# StickLogger.net
KiCad netlist of a schematic drawn in EAGLE
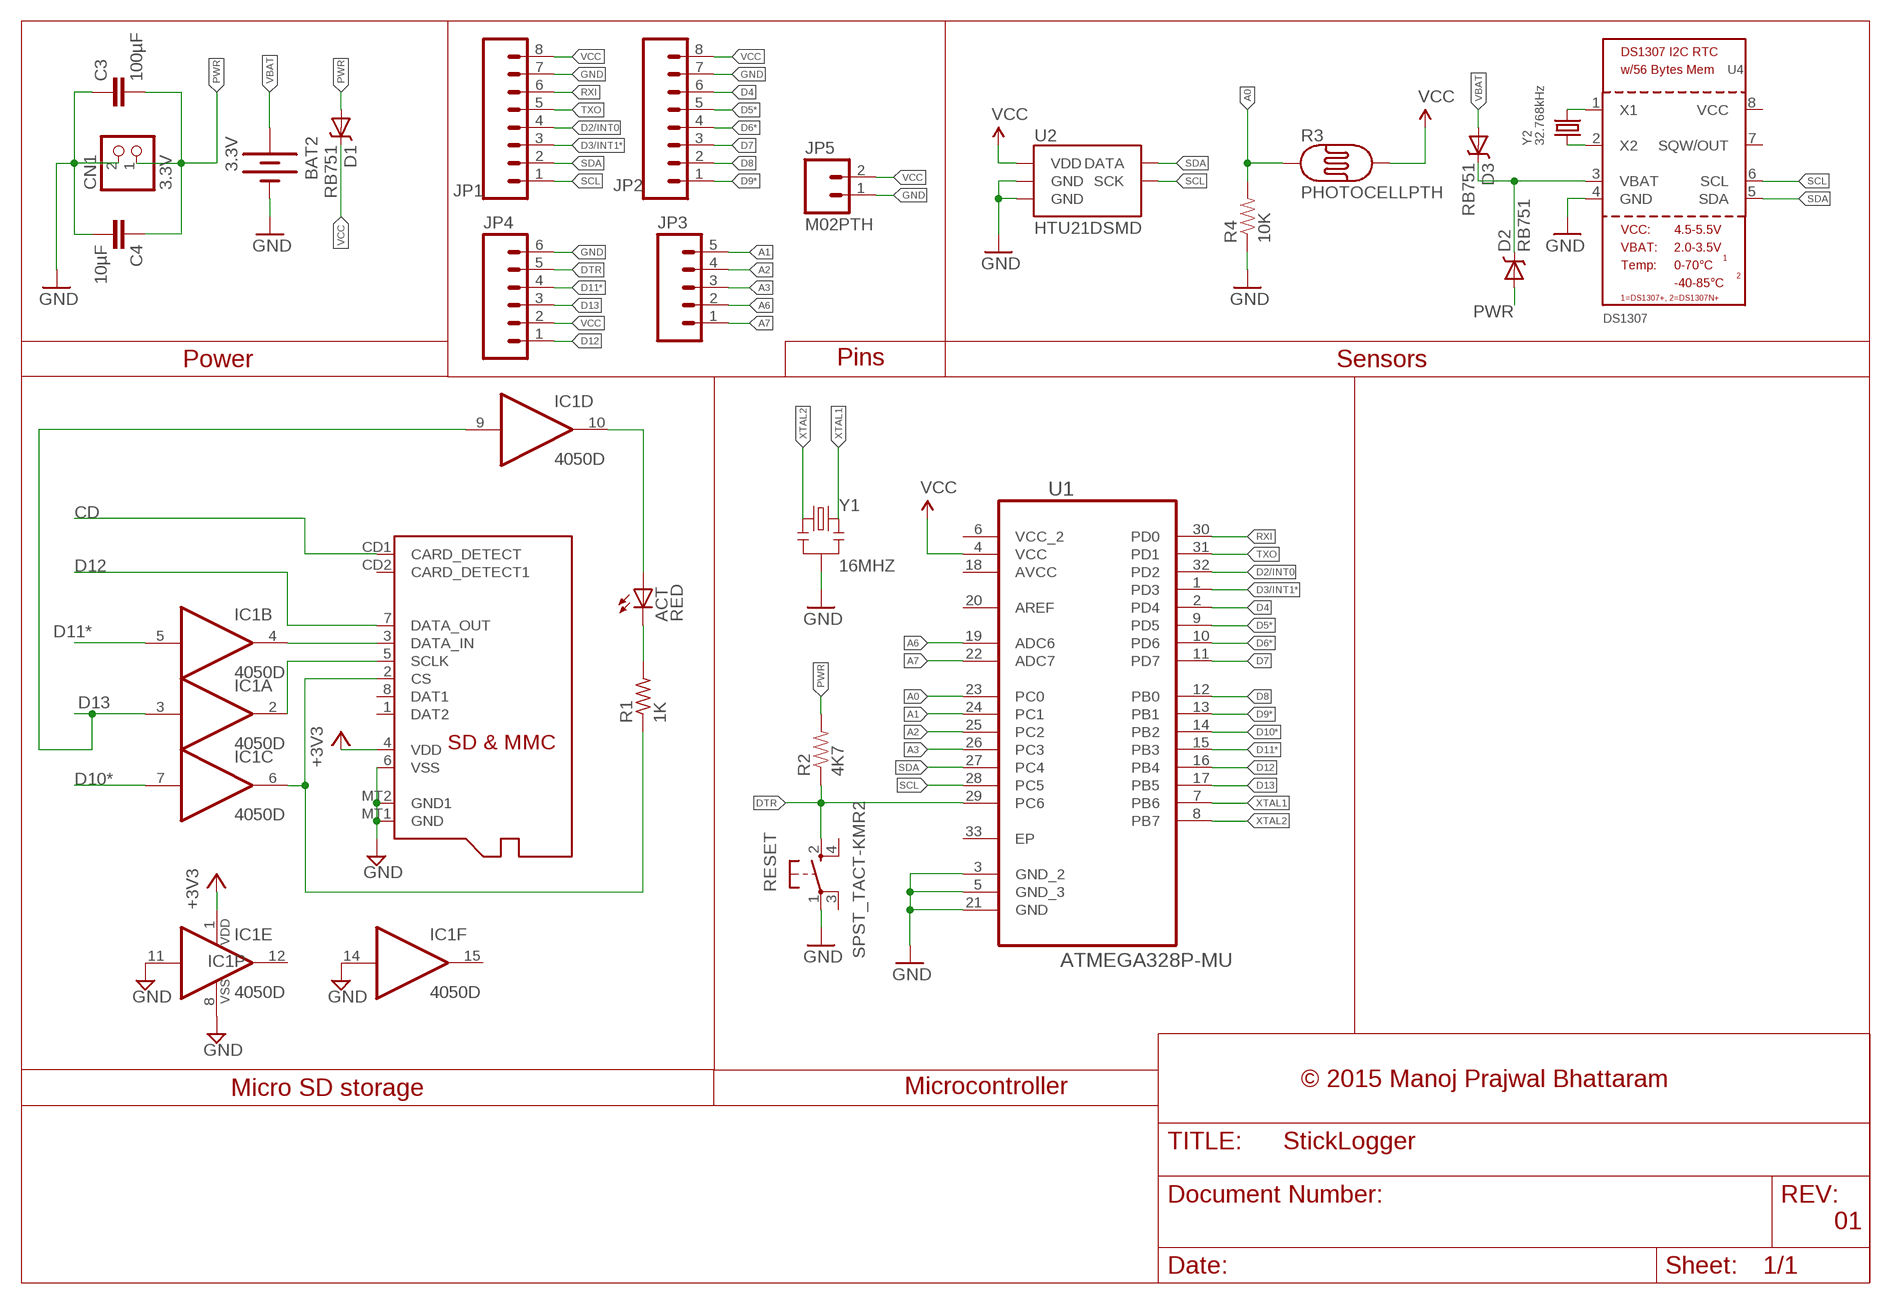
[diagram p0: schematic, sheet 1]

(export (version "E")
  (design (tool "Eeschema 10.0.6"))
  (components
    (comp (ref "ACT")
      (value "RED")
      (footprint "eagle-import:CHIP-LED0805")
      (libsource (lib "eagle-import") (part "LEDCHIP-LED0805"))
    )
    (comp (ref "BAT2")
      (value "3.3V")
      (footprint "eagle-import:BATTCON_12MM")
      (libsource (lib "eagle-import") (part "BATTERY12MM"))
    )
    (comp (ref "C3")
      (value "100µF")
      (footprint "eagle-import:0402-CAP")
      (libsource (lib "eagle-import") (part "CAP0402-CAP"))
    )
    (comp (ref "C4")
      (value "10µF")
      (footprint "eagle-import:0402-CAP")
      (libsource (lib "eagle-import") (part "CAP0402-CAP"))
    )
    (comp (ref "CN1")
      (value "3.3V")
      (footprint "eagle-import:JST-PH-2-SMT-RA")
      (libsource (lib "eagle-import") (part "JST_2PIN-SMT-RA"))
    )
    (comp (ref "D1")
      (value "RB751")
      (footprint "eagle-import:SOD-523")
      (libsource (lib "eagle-import") (part "DIODE-SCHOTTKY-RB751"))
    )
    (comp (ref "D2")
      (value "RB751")
      (footprint "eagle-import:SOD-523")
      (libsource (lib "eagle-import") (part "DIODE-SCHOTTKY-RB751"))
    )
    (comp (ref "D3")
      (value "RB751")
      (footprint "eagle-import:SOD-523")
      (libsource (lib "eagle-import") (part "DIODE-SCHOTTKY-RB751"))
    )
    (comp (ref "IC1")
      (value "4050D")
      (footprint "eagle-import:SO16")
      (libsource (lib "eagle-import") (part "4050D"))
    )
    (comp (ref "JP1")
      (value "M08NO_SILK")
      (footprint "eagle-import:1X08_NO_SILK")
      (libsource (lib "eagle-import") (part "M08NO_SILK"))
    )
    (comp (ref "JP2")
      (value "M08NO_SILK")
      (footprint "eagle-import:1X08_NO_SILK")
      (libsource (lib "eagle-import") (part "M08NO_SILK"))
    )
    (comp (ref "JP3")
      (value "M05NO_SILK")
      (footprint "eagle-import:1X05_NO_SILK")
      (libsource (lib "eagle-import") (part "M05NO_SILK"))
    )
    (comp (ref "JP4")
      (value "M06SMD")
      (footprint "eagle-import:1X06-SMD")
      (libsource (lib "eagle-import") (part "M06SMD"))
    )
    (comp (ref "JP5")
      (value "M02PTH")
      (footprint "eagle-import:1X02")
      (libsource (lib "eagle-import") (part "M02PTH"))
    )
    (comp (ref "R1")
      (value "1K")
      (footprint "eagle-import:R0805")
      (libsource (lib "eagle-import") (part "R-US_R0805"))
    )
    (comp (ref "R2")
      (value "4K7")
      (footprint "eagle-import:0402-RES")
      (libsource (lib "eagle-import") (part "RESISTOR0402-RES"))
    )
    (comp (ref "R3")
      (value "PHOTOCELLPTH")
      (footprint "eagle-import:PHOTOCELL")
      (libsource (lib "eagle-import") (part "PHOTOCELLPTH"))
    )
    (comp (ref "R4")
      (value "10K")
      (footprint "eagle-import:0402-RES")
      (libsource (lib "eagle-import") (part "RESISTOR0402-RES"))
    )
    (comp (ref "RESET")
      (value "SPST_TACT-KMR2")
      (footprint "eagle-import:KMR2")
      (libsource (lib "eagle-import") (part "SPST_TACT-KMR2"))
    )
    (comp (ref "U1")
      (value "ATMEGA328P-MU")
      (footprint "eagle-import:QFN50P500X500X100-33N")
      (libsource (lib "eagle-import") (part "ATMEGA328P-MU"))
    )
    (comp (ref "U2")
      (value "HTU21DSMD")
      (footprint "eagle-import:HTU21D")
      (libsource (lib "eagle-import") (part "HTU21DSMD"))
    )
    (comp (ref "U4")
      (value "DS1307")
      (footprint "eagle-import:SOIC8_150MIL")
      (libsource (lib "eagle-import") (part "RTC_DS1307"))
    )
    (comp (ref "X1")
      (value "MICROSD")
      (footprint "eagle-import:MICROSD")
      (libsource (lib "eagle-import") (part "MICROSD"))
    )
    (comp (ref "Y1")
      (value "16MHZ")
      (footprint "eagle-import:RESONATOR-SMD")
      (libsource (lib "eagle-import") (part "RESONATOR16MHZ"))
    )
    (comp (ref "Y2")
      (value "32.768kHz")
      (footprint "eagle-import:CRYSTAL-32KHZ-SMD")
      (libsource (lib "eagle-import") (part "CRYSTAL32-SMD"))
    )
  )
  (nets
    (net (code "1") (name "+3V3") (class "Default")
      (node (ref "IC1") (pin "1") (pinfunction "VDD_1") (pintype "power_in"))
      (node (ref "X1") (pin "4") (pinfunction "VDD_4") (pintype "power_in"))
    )
    (net (code "2") (name "/AVCC") (class "Default")
      (node (ref "U1") (pin "18") (pinfunction "AVCC_18") (pintype "power_in"))
    )
    (net (code "3") (name "/CD") (class "Default")
      (node (ref "X1") (pin "CD1") (pinfunction "CARD_DETECT_CD1") (pintype "passive"))
    )
    (net (code "4") (name "/VCC_2") (class "Default")
      (node (ref "U1") (pin "6") (pinfunction "VCC_2_6") (pintype "power_in"))
    )
    (net (code "5") (name "A0") (class "Default")
      (node (ref "R3") (pin "1") (pinfunction "P$1_1") (pintype "bidirectional"))
      (node (ref "R4") (pin "2") (pinfunction "2_2") (pintype "passive"))
      (node (ref "U1") (pin "23") (pinfunction "PC0_23") (pintype "bidirectional"))
    )
    (net (code "6") (name "A1") (class "Default")
      (node (ref "JP3") (pin "5") (pinfunction "5_5") (pintype "passive"))
      (node (ref "U1") (pin "24") (pinfunction "PC1_24") (pintype "bidirectional"))
    )
    (net (code "7") (name "A2") (class "Default")
      (node (ref "JP3") (pin "4") (pinfunction "4_4") (pintype "passive"))
      (node (ref "U1") (pin "25") (pinfunction "PC2_25") (pintype "bidirectional"))
    )
    (net (code "8") (name "A3") (class "Default")
      (node (ref "JP3") (pin "3") (pinfunction "3_3") (pintype "passive"))
      (node (ref "U1") (pin "26") (pinfunction "PC3_26") (pintype "bidirectional"))
    )
    (net (code "9") (name "A6") (class "Default")
      (node (ref "JP3") (pin "2") (pinfunction "2_2") (pintype "passive"))
      (node (ref "U1") (pin "19") (pinfunction "ADC6_19") (pintype "input"))
    )
    (net (code "10") (name "A7") (class "Default")
      (node (ref "JP3") (pin "1") (pinfunction "1_1") (pintype "passive"))
      (node (ref "U1") (pin "22") (pinfunction "ADC7_22") (pintype "input"))
    )
    (net (code "11") (name "D2{slash}INT0") (class "Default")
      (node (ref "JP1") (pin "4") (pinfunction "4_4") (pintype "passive"))
      (node (ref "U1") (pin "32") (pinfunction "PD2_32") (pintype "bidirectional"))
    )
    (net (code "12") (name "D3{slash}INT1*") (class "Default")
      (node (ref "JP1") (pin "3") (pinfunction "3_3") (pintype "passive"))
      (node (ref "U1") (pin "1") (pinfunction "PD3_1") (pintype "bidirectional"))
    )
    (net (code "13") (name "D4") (class "Default")
      (node (ref "JP2") (pin "6") (pinfunction "6_6") (pintype "passive"))
      (node (ref "U1") (pin "2") (pinfunction "PD4_2") (pintype "bidirectional"))
    )
    (net (code "14") (name "D5*") (class "Default")
      (node (ref "JP2") (pin "5") (pinfunction "5_5") (pintype "passive"))
      (node (ref "U1") (pin "9") (pinfunction "PD5_9") (pintype "bidirectional"))
    )
    (net (code "15") (name "D6*") (class "Default")
      (node (ref "JP2") (pin "4") (pinfunction "4_4") (pintype "passive"))
      (node (ref "U1") (pin "10") (pinfunction "PD6_10") (pintype "bidirectional"))
    )
    (net (code "16") (name "D7") (class "Default")
      (node (ref "JP2") (pin "3") (pinfunction "3_3") (pintype "passive"))
      (node (ref "U1") (pin "11") (pinfunction "PD7_11") (pintype "bidirectional"))
    )
    (net (code "17") (name "D8") (class "Default")
      (node (ref "JP2") (pin "2") (pinfunction "2_2") (pintype "passive"))
      (node (ref "U1") (pin "12") (pinfunction "PB0_12") (pintype "bidirectional"))
    )
    (net (code "18") (name "D9*") (class "Default")
      (node (ref "JP2") (pin "1") (pinfunction "1_1") (pintype "passive"))
      (node (ref "U1") (pin "13") (pinfunction "PB1_13") (pintype "bidirectional"))
    )
    (net (code "19") (name "D10*") (class "Default")
      (node (ref "IC1") (pin "7") (pinfunction "I_7") (pintype "input"))
      (node (ref "U1") (pin "14") (pinfunction "PB2_14") (pintype "bidirectional"))
    )
    (net (code "20") (name "D11*") (class "Default")
      (node (ref "IC1") (pin "5") (pinfunction "I_5") (pintype "input"))
      (node (ref "JP4") (pin "4") (pinfunction "4_4") (pintype "passive"))
      (node (ref "U1") (pin "15") (pinfunction "PB3_15") (pintype "bidirectional"))
    )
    (net (code "21") (name "D12") (class "Default")
      (node (ref "JP4") (pin "1") (pinfunction "1_1") (pintype "passive"))
      (node (ref "U1") (pin "16") (pinfunction "PB4_16") (pintype "bidirectional"))
      (node (ref "X1") (pin "7") (pinfunction "DATA_OUT_7") (pintype "output"))
    )
    (net (code "22") (name "D13") (class "Default")
      (node (ref "IC1") (pin "3") (pinfunction "I_3") (pintype "input"))
      (node (ref "IC1") (pin "9") (pinfunction "I_9") (pintype "input"))
      (node (ref "JP4") (pin "3") (pinfunction "3_3") (pintype "passive"))
      (node (ref "U1") (pin "17") (pinfunction "PB5_17") (pintype "bidirectional"))
    )
    (net (code "23") (name "DTR") (class "Default")
      (node (ref "JP4") (pin "5") (pinfunction "5_5") (pintype "passive"))
      (node (ref "R2") (pin "1") (pinfunction "1_1") (pintype "passive"))
      (node (ref "RESET") (pin "2") (pinfunction "S_2") (pintype "passive"))
      (node (ref "U1") (pin "29") (pinfunction "PC6_29") (pintype "bidirectional"))
    )
    (net (code "24") (name "GND") (class "Default")
      (node (ref "BAT2") (pin "GND") (pinfunction "-_GND") (pintype "power_in"))
      (node (ref "C3") (pin "1") (pinfunction "1_1") (pintype "passive"))
      (node (ref "C4") (pin "2") (pinfunction "2_2") (pintype "passive"))
      (node (ref "CN1") (pin "2") (pinfunction "1_2") (pintype "passive"))
      (node (ref "IC1") (pin "11") (pinfunction "I_11") (pintype "input"))
      (node (ref "IC1") (pin "14") (pinfunction "I_14") (pintype "input"))
      (node (ref "IC1") (pin "8") (pinfunction "VSS_8") (pintype "power_in"))
      (node (ref "JP1") (pin "7") (pinfunction "7_7") (pintype "passive"))
      (node (ref "JP2") (pin "7") (pinfunction "7_7") (pintype "passive"))
      (node (ref "JP4") (pin "6") (pinfunction "6_6") (pintype "passive"))
      (node (ref "JP5") (pin "1") (pinfunction "1_1") (pintype "passive"))
      (node (ref "R4") (pin "1") (pinfunction "1_1") (pintype "passive"))
      (node (ref "RESET") (pin "1") (pinfunction "P_1") (pintype "passive"))
      (node (ref "U1") (pin "21") (pinfunction "GND_21") (pintype "passive"))
      (node (ref "U1") (pin "3") (pinfunction "GND_2_3") (pintype "passive"))
      (node (ref "U1") (pin "5") (pinfunction "GND_3_5") (pintype "passive"))
      (node (ref "U2") (pin "7") (pinfunction "GND_7") (pintype "power_in"))
      (node (ref "U2") (pin "GND") (pinfunction "GND_GND") (pintype "power_in"))
      (node (ref "U4") (pin "4") (pinfunction "GND_4") (pintype "bidirectional"))
      (node (ref "X1") (pin "6") (pinfunction "VSS_6") (pintype "power_in"))
      (node (ref "X1") (pin "MT1") (pinfunction "GND_MT1") (pintype "power_in"))
      (node (ref "X1") (pin "MT2") (pinfunction "GND1_MT2") (pintype "power_in"))
      (node (ref "Y1") (pin "2") (pinfunction "2_2") (pintype "passive"))
    )
    (net (code "25") (name "Net-(ACT-PadC)") (class "Default")
      (node (ref "ACT") (pin "C") (pinfunction "C_C") (pintype "passive"))
      (node (ref "R1") (pin "2") (pinfunction "2_2") (pintype "passive"))
    )
    (net (code "26") (name "Net-(IC1A-O)") (class "Default")
      (node (ref "IC1") (pin "2") (pinfunction "O_2") (pintype "output"))
      (node (ref "X1") (pin "5") (pinfunction "SCLK_5") (pintype "input"))
    )
    (net (code "27") (name "Net-(IC1B-O)") (class "Default")
      (node (ref "IC1") (pin "4") (pinfunction "O_4") (pintype "output"))
      (node (ref "X1") (pin "3") (pinfunction "DATA_IN_3") (pintype "input"))
    )
    (net (code "28") (name "Net-(IC1C-O)") (class "Default")
      (node (ref "IC1") (pin "6") (pinfunction "O_6") (pintype "output"))
      (node (ref "R1") (pin "1") (pinfunction "1_1") (pintype "passive"))
      (node (ref "X1") (pin "2") (pinfunction "CS_2") (pintype "input"))
    )
    (net (code "29") (name "Net-(IC1D-O)") (class "Default")
      (node (ref "ACT") (pin "A") (pinfunction "A_A") (pintype "passive"))
      (node (ref "IC1") (pin "10") (pinfunction "O_10") (pintype "output"))
    )
    (net (code "30") (name "Net-(U4-VBAT)") (class "Default")
      (node (ref "D2") (pin "C") (pinfunction "C_C") (pintype "passive"))
      (node (ref "D3") (pin "C") (pinfunction "C_C") (pintype "passive"))
      (node (ref "U4") (pin "3") (pinfunction "VBAT_3") (pintype "bidirectional"))
    )
    (net (code "31") (name "Net-(U4-X1)") (class "Default")
      (node (ref "U4") (pin "1") (pinfunction "X1_1") (pintype "bidirectional"))
      (node (ref "Y2") (pin "X2") (pinfunction "2_X2") (pintype "passive"))
    )
    (net (code "32") (name "Net-(U4-X2)") (class "Default")
      (node (ref "U4") (pin "2") (pinfunction "X2_2") (pintype "bidirectional"))
      (node (ref "Y2") (pin "X1") (pinfunction "1_X1") (pintype "passive"))
    )
    (net (code "33") (name "PWR") (class "Default")
      (node (ref "C3") (pin "2") (pinfunction "2_2") (pintype "passive"))
      (node (ref "C4") (pin "1") (pinfunction "1_1") (pintype "passive"))
      (node (ref "CN1") (pin "1") (pinfunction "2_1") (pintype "passive"))
      (node (ref "D1") (pin "A") (pinfunction "A_A") (pintype "passive"))
      (node (ref "D2") (pin "A") (pinfunction "A_A") (pintype "passive"))
      (node (ref "R2") (pin "2") (pinfunction "2_2") (pintype "passive"))
    )
    (net (code "34") (name "RXI") (class "Default")
      (node (ref "JP1") (pin "6") (pinfunction "6_6") (pintype "passive"))
      (node (ref "U1") (pin "30") (pinfunction "PD0_30") (pintype "bidirectional"))
    )
    (net (code "35") (name "SCL") (class "Default")
      (node (ref "JP1") (pin "1") (pinfunction "1_1") (pintype "passive"))
      (node (ref "U1") (pin "28") (pinfunction "PC5_28") (pintype "bidirectional"))
      (node (ref "U2") (pin "SCK") (pinfunction "SCK_SCK") (pintype "input"))
      (node (ref "U4") (pin "6") (pinfunction "SCL_6") (pintype "bidirectional"))
    )
    (net (code "36") (name "SDA") (class "Default")
      (node (ref "JP1") (pin "2") (pinfunction "2_2") (pintype "passive"))
      (node (ref "U1") (pin "27") (pinfunction "PC4_27") (pintype "bidirectional"))
      (node (ref "U2") (pin "DATA") (pinfunction "DATA_DATA") (pintype "bidirectional"))
      (node (ref "U4") (pin "5") (pinfunction "SDA_5") (pintype "bidirectional"))
    )
    (net (code "37") (name "TXO") (class "Default")
      (node (ref "JP1") (pin "5") (pinfunction "5_5") (pintype "passive"))
      (node (ref "U1") (pin "31") (pinfunction "PD1_31") (pintype "bidirectional"))
    )
    (net (code "38") (name "VBAT") (class "Default")
      (node (ref "BAT2") (pin "PWR@1") (pinfunction "+_PWR@1") (pintype "power_in"))
      (node (ref "D3") (pin "A") (pinfunction "A_A") (pintype "passive"))
    )
    (net (code "39") (name "VCC") (class "Default")
      (node (ref "D1") (pin "C") (pinfunction "C_C") (pintype "passive"))
      (node (ref "JP1") (pin "8") (pinfunction "8_8") (pintype "passive"))
      (node (ref "JP2") (pin "8") (pinfunction "8_8") (pintype "passive"))
      (node (ref "JP4") (pin "2") (pinfunction "2_2") (pintype "passive"))
      (node (ref "JP5") (pin "2") (pinfunction "2_2") (pintype "passive"))
      (node (ref "R3") (pin "2") (pinfunction "P$2_2") (pintype "bidirectional"))
      (node (ref "U1") (pin "4") (pinfunction "VCC_4") (pintype "power_in"))
      (node (ref "U2") (pin "VDD") (pinfunction "VDD_VDD") (pintype "power_in"))
    )
    (net (code "40") (name "XTAL1") (class "Default")
      (node (ref "U1") (pin "7") (pinfunction "PB6_7") (pintype "bidirectional"))
      (node (ref "Y1") (pin "3") (pinfunction "3_3") (pintype "passive"))
    )
    (net (code "41") (name "XTAL2") (class "Default")
      (node (ref "U1") (pin "8") (pinfunction "PB7_8") (pintype "bidirectional"))
      (node (ref "Y1") (pin "1") (pinfunction "1_1") (pintype "passive"))
    )
    (net (code "42") (name "unconnected-(IC1E-O-Pad12)") (class "Default")
      (node (ref "IC1") (pin "12") (pinfunction "O_12") (pintype "output"))
    )
    (net (code "43") (name "unconnected-(IC1F-O-Pad15)") (class "Default")
      (node (ref "IC1") (pin "15") (pinfunction "O_15") (pintype "output"))
    )
    (net (code "44") (name "unconnected-(RESET-P1-Pad3)") (class "Default")
      (node (ref "RESET") (pin "3") (pinfunction "P1_3") (pintype "passive"))
    )
    (net (code "45") (name "unconnected-(RESET-S1-Pad4)") (class "Default")
      (node (ref "RESET") (pin "4") (pinfunction "S1_4") (pintype "passive"))
    )
    (net (code "46") (name "unconnected-(U1-AREF-Pad20)") (class "Default")
      (node (ref "U1") (pin "20") (pinfunction "AREF_20") (pintype "input"))
    )
    (net (code "47") (name "unconnected-(U1-EP-Pad33)") (class "Default")
      (node (ref "U1") (pin "33") (pinfunction "EP_33") (pintype "passive"))
    )
    (net (code "48") (name "unconnected-(U4-SQW{slash}OUT-Pad7)") (class "Default")
      (node (ref "U4") (pin "7") (pinfunction "SQW/OUT_7") (pintype "bidirectional"))
    )
    (net (code "49") (name "unconnected-(U4-VCC-Pad8)") (class "Default")
      (node (ref "U4") (pin "8") (pinfunction "VCC_8") (pintype "bidirectional"))
    )
    (net (code "50") (name "unconnected-(X1-CARD_DETECT1-PadCD2)") (class "Default")
      (node (ref "X1") (pin "CD2") (pinfunction "CARD_DETECT1_CD2") (pintype "passive"))
    )
    (net (code "51") (name "unconnected-(X1-DAT1-Pad8)") (class "Default")
      (node (ref "X1") (pin "8") (pinfunction "DAT1_8") (pintype "bidirectional"))
    )
    (net (code "52") (name "unconnected-(X1-DAT2-Pad1)") (class "Default")
      (node (ref "X1") (pin "1") (pinfunction "DAT2_1") (pintype "bidirectional"))
    )
  )
)
